# design.net
KiCad netlist of a schematic drawn in Altium Designer
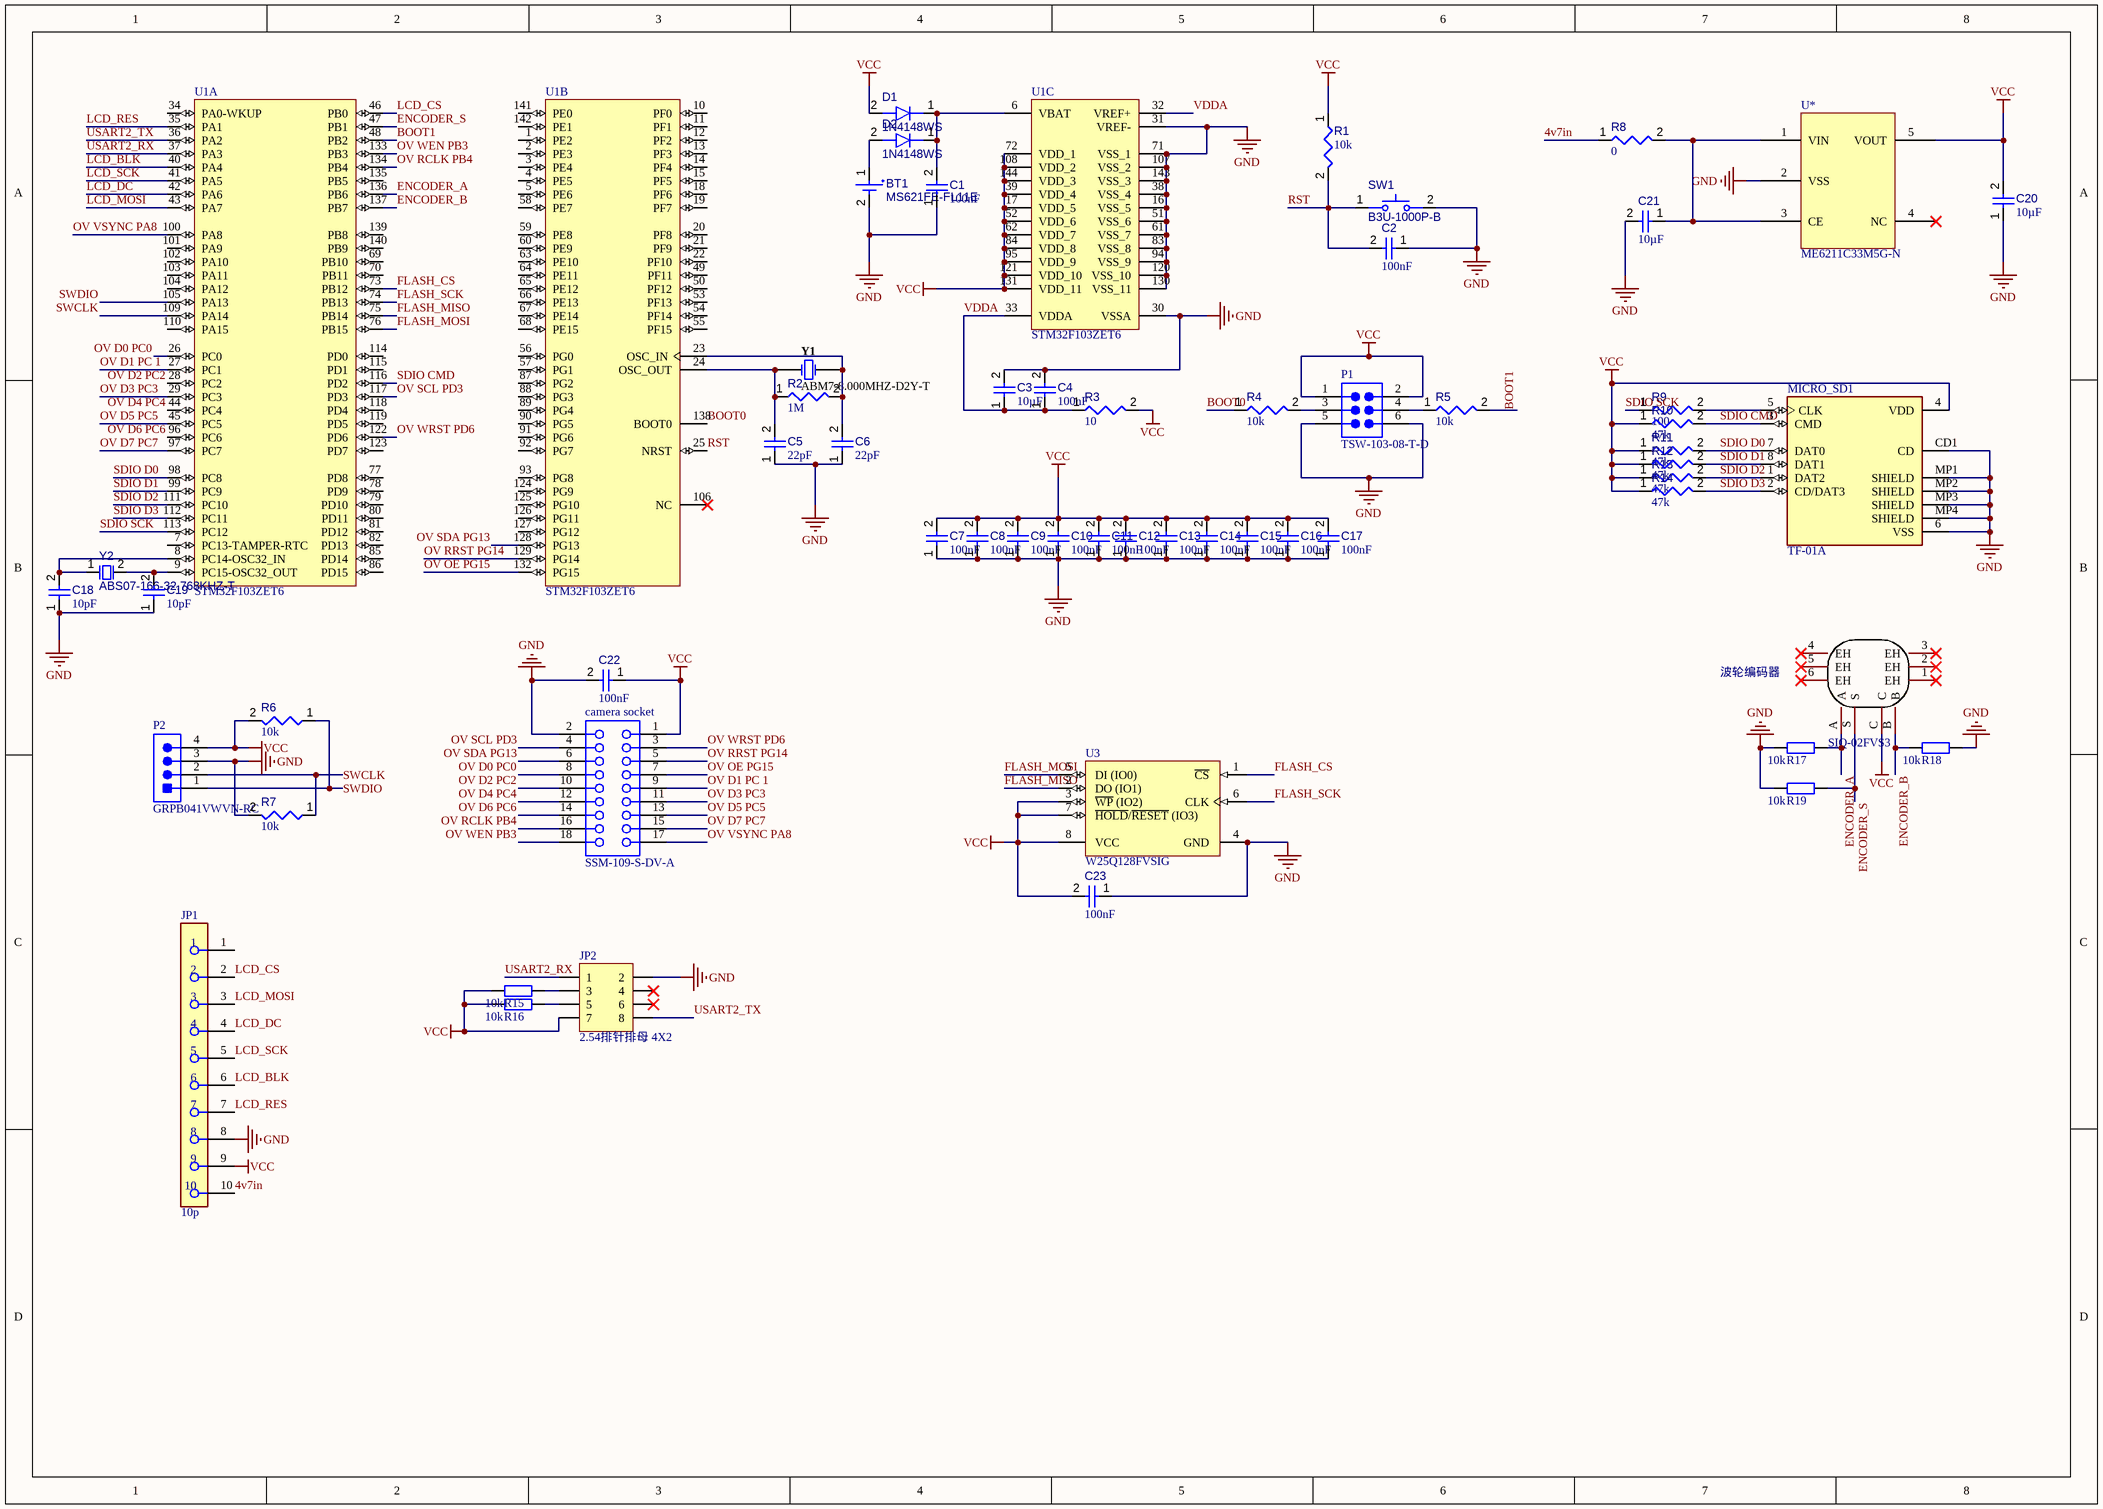
[diagram p0: 前板.SchDoc]

(export (version "E")
  (design (tool "Eeschema 10.0.6"))
  (components
    (comp (ref "BT1")
      (value "MS621FE-FL11E")
      (footprint "SEIK-MS621FE-FL11E-2_V")
      (description "MS Lihium Rechargeable Battery, 3 V, -20 to 60 degC, Tray")
      (libsource (lib "DigiPCBA Workspace") (part "CMP-00622-2"))
    )
    (comp (ref "C1")
      (value "100nF")
      (footprint "CAPC1608X90X40NL10T20")
      (description "Chip Capacitor, 100 nF, +/- 10%, 50 V, 0603 (1608 Metric)")
      (fields (field (name "TOLERANCE") "10%") (field (name "Comment") "Capacitor 100 nF +/-10% 50 V 0603"))
      (libsource (lib "DigiPCBA Workspace") (part "CAP-NP-2"))
    )
    (comp (ref "C2")
      (value "100nF")
      (footprint "CAPC1608X90X40NL10T20")
      (description "Chip Capacitor, 100 nF, +/- 10%, 50 V, 0603 (1608 Metric)")
      (fields (field (name "TOLERANCE") "10%") (field (name "Comment") "Capacitor 100 nF +/-10% 50 V 0603"))
      (libsource (lib "DigiPCBA Workspace") (part "CAP-NP-2"))
    )
    (comp (ref "C3")
      (value "10µF")
      (footprint "CAPC0603(1608)100_L")
      (description "Chip Capacitor, 10µF +/-20%, 10V, 0603, Thickness 1 mm")
      (fields (field (name "TOLERANCE") "10%") (field (name "Comment") "Capacitor 10µF +/-20% 10V 0603"))
      (libsource (lib "DigiPCBA Workspace") (part "CAP-NP-2"))
    )
    (comp (ref "C4")
      (value "100nF")
      (footprint "CAPC1608X90X40NL10T20")
      (description "Chip Capacitor, 100 nF, +/- 10%, 50 V, 0603 (1608 Metric)")
      (fields (field (name "TOLERANCE") "10%") (field (name "Comment") "Capacitor 100 nF +/-10% 50 V 0603"))
      (libsource (lib "DigiPCBA Workspace") (part "CAP-NP-2"))
    )
    (comp (ref "C5")
      (value "22pF")
      (footprint "CAPC1608X90X35ML10T15")
      (description "CAP CER 22PF 50V C0G/NP0 0603")
      (fields (field (name "TOLERANCE") "10%") (field (name "Comment") "GRM1885C1H220JA01D"))
      (libsource (lib "DigiPCBA Workspace") (part "CAP-NP-2"))
    )
    (comp (ref "C6")
      (value "22pF")
      (footprint "CAPC1608X90X35ML10T15")
      (description "CAP CER 22PF 50V C0G/NP0 0603")
      (fields (field (name "TOLERANCE") "10%") (field (name "Comment") "GRM1885C1H220JA01D"))
      (libsource (lib "DigiPCBA Workspace") (part "CAP-NP-2"))
    )
    (comp (ref "C7")
      (value "100nF")
      (footprint "CAPC1608X90X40NL10T20")
      (description "Chip Capacitor, 100 nF, +/- 10%, 50 V, 0603 (1608 Metric)")
      (fields (field (name "TOLERANCE") "10%") (field (name "Comment") "Capacitor 100 nF +/-10% 50 V 0603"))
      (libsource (lib "DigiPCBA Workspace") (part "CAP-NP-2"))
    )
    (comp (ref "C8")
      (value "100nF")
      (footprint "CAPC1608X90X40NL10T20")
      (description "Chip Capacitor, 100 nF, +/- 10%, 50 V, 0603 (1608 Metric)")
      (fields (field (name "TOLERANCE") "10%") (field (name "Comment") "Capacitor 100 nF +/-10% 50 V 0603"))
      (libsource (lib "DigiPCBA Workspace") (part "CAP-NP-2"))
    )
    (comp (ref "C9")
      (value "100nF")
      (footprint "CAPC1608X90X40NL10T20")
      (description "Chip Capacitor, 100 nF, +/- 10%, 50 V, 0603 (1608 Metric)")
      (fields (field (name "TOLERANCE") "10%") (field (name "Comment") "Capacitor 100 nF +/-10% 50 V 0603"))
      (libsource (lib "DigiPCBA Workspace") (part "CAP-NP-2"))
    )
    (comp (ref "C10")
      (value "100nF")
      (footprint "CAPC1608X90X40NL10T20")
      (description "Chip Capacitor, 100 nF, +/- 10%, 50 V, 0603 (1608 Metric)")
      (fields (field (name "TOLERANCE") "10%") (field (name "Comment") "Capacitor 100 nF +/-10% 50 V 0603"))
      (libsource (lib "DigiPCBA Workspace") (part "CAP-NP-2"))
    )
    (comp (ref "C11")
      (value "100nF")
      (footprint "CAPC1608X90X40NL10T20")
      (description "Chip Capacitor, 100 nF, +/- 10%, 50 V, 0603 (1608 Metric)")
      (fields (field (name "TOLERANCE") "10%") (field (name "Comment") "Capacitor 100 nF +/-10% 50 V 0603"))
      (libsource (lib "DigiPCBA Workspace") (part "CAP-NP-2"))
    )
    (comp (ref "C12")
      (value "100nF")
      (footprint "CAPC1608X90X40NL10T20")
      (description "Chip Capacitor, 100 nF, +/- 10%, 50 V, 0603 (1608 Metric)")
      (fields (field (name "TOLERANCE") "10%") (field (name "Comment") "Capacitor 100 nF +/-10% 50 V 0603"))
      (libsource (lib "DigiPCBA Workspace") (part "CAP-NP-2"))
    )
    (comp (ref "C13")
      (value "100nF")
      (footprint "CAPC1608X90X40NL10T20")
      (description "Chip Capacitor, 100 nF, +/- 10%, 50 V, 0603 (1608 Metric)")
      (fields (field (name "TOLERANCE") "10%") (field (name "Comment") "Capacitor 100 nF +/-10% 50 V 0603"))
      (libsource (lib "DigiPCBA Workspace") (part "CAP-NP-2"))
    )
    (comp (ref "C14")
      (value "100nF")
      (footprint "CAPC1608X90X40NL10T20")
      (description "Chip Capacitor, 100 nF, +/- 10%, 50 V, 0603 (1608 Metric)")
      (fields (field (name "TOLERANCE") "10%") (field (name "Comment") "Capacitor 100 nF +/-10% 50 V 0603"))
      (libsource (lib "DigiPCBA Workspace") (part "CAP-NP-2"))
    )
    (comp (ref "C15")
      (value "100nF")
      (footprint "CAPC1608X90X40NL10T20")
      (description "Chip Capacitor, 100 nF, +/- 10%, 50 V, 0603 (1608 Metric)")
      (fields (field (name "TOLERANCE") "10%") (field (name "Comment") "Capacitor 100 nF +/-10% 50 V 0603"))
      (libsource (lib "DigiPCBA Workspace") (part "CAP-NP-2"))
    )
    (comp (ref "C16")
      (value "100nF")
      (footprint "CAPC1608X90X40NL10T20")
      (description "Chip Capacitor, 100 nF, +/- 10%, 50 V, 0603 (1608 Metric)")
      (fields (field (name "TOLERANCE") "10%") (field (name "Comment") "Capacitor 100 nF +/-10% 50 V 0603"))
      (libsource (lib "DigiPCBA Workspace") (part "CAP-NP-2"))
    )
    (comp (ref "C17")
      (value "100nF")
      (footprint "CAPC1608X90X40NL10T20")
      (description "Chip Capacitor, 100 nF, +/- 10%, 50 V, 0603 (1608 Metric)")
      (fields (field (name "TOLERANCE") "10%") (field (name "Comment") "Capacitor 100 nF +/-10% 50 V 0603"))
      (libsource (lib "DigiPCBA Workspace") (part "CAP-NP-2"))
    )
    (comp (ref "C18")
      (value "10pF")
      (footprint "CAPC1005X55X25ML05T05")
      (description "Chip Capacitor, 10 pF, +/- 5%, 50 V, 0402 (1005 Metric)")
      (fields (field (name "TOLERANCE") "5%") (field (name "Comment") "Capacitor 10 pF +/- 5% 50 V 0402"))
      (libsource (lib "DigiPCBA Workspace") (part "CAP-NP-2"))
    )
    (comp (ref "C19")
      (value "10pF")
      (footprint "CAPC1005X55X25ML05T05")
      (description "Chip Capacitor, 10 pF, +/- 5%, 50 V, 0402 (1005 Metric)")
      (fields (field (name "TOLERANCE") "5%") (field (name "Comment") "Capacitor 10 pF +/- 5% 50 V 0402"))
      (libsource (lib "DigiPCBA Workspace") (part "CAP-NP-2"))
    )
    (comp (ref "C20")
      (value "10µF")
      (footprint "CAPC0603(1608)100_L")
      (description "Chip Capacitor, 10µF +/-20%, 10V, 0603, Thickness 1 mm")
      (fields (field (name "TOLERANCE") "10%") (field (name "Comment") "Capacitor 10µF +/-20% 10V 0603"))
      (libsource (lib "DigiPCBA Workspace") (part "CAP-NP-2"))
    )
    (comp (ref "C21")
      (value "10µF")
      (footprint "CAPC0603(1608)100_L")
      (description "Chip Capacitor, 10µF +/-20%, 10V, 0603, Thickness 1 mm")
      (fields (field (name "TOLERANCE") "10%") (field (name "Comment") "Capacitor 10µF +/-20% 10V 0603"))
      (libsource (lib "DigiPCBA Workspace") (part "CAP-NP-2"))
    )
    (comp (ref "C22")
      (value "100nF")
      (footprint "CAPC1608X90X40NL10T20")
      (description "Chip Capacitor, 100 nF, +/- 10%, 50 V, 0603 (1608 Metric)")
      (fields (field (name "TOLERANCE") "10%") (field (name "Comment") "Capacitor 100 nF +/-10% 50 V 0603"))
      (libsource (lib "DigiPCBA Workspace") (part "CAP-NP-2"))
    )
    (comp (ref "C23")
      (value "100nF")
      (footprint "CAPC1608X90X40NL10T20")
      (description "Chip Capacitor, 100 nF, +/- 10%, 50 V, 0603 (1608 Metric)")
      (fields (field (name "TOLERANCE") "10%") (field (name "Comment") "Capacitor 100 nF +/-10% 50 V 0603"))
      (libsource (lib "DigiPCBA Workspace") (part "CAP-NP-2"))
    )
    (comp (ref "camera socket")
      (value "SSM-109-S-DV-A")
      (footprint "SMTC-SSM-109-X-DV-A")
      (description "Headers & Wire Housings Surface Mount PCB Socket Strips, 0.100 pitch")
      (libsource (lib "DigiPCBA Workspace") (part "SMTC-SSM-109-X-DV-A"))
    )
    (comp (ref "D1")
      (value "1N4148WS")
      (footprint "FP-477AB-IPC_A")
      (description "Diode Ultra Fast Recovery Rectifier 75V 0.15A 2-Pin SOD-323F T/R")
      (libsource (lib "DigiPCBA Workspace") (part "DIODE-2"))
    )
    (comp (ref "D2")
      (value "1N4148WS")
      (footprint "FP-477AB-IPC_A")
      (description "Diode Ultra Fast Recovery Rectifier 75V 0.15A 2-Pin SOD-323F T/R")
      (libsource (lib "DigiPCBA Workspace") (part "DIODE-2"))
    )
    (comp (ref "JP1")
      (value "10p")
      (footprint "XH2.54-WI-10P")
      (fields (field (name "SOURCE") "线对板线对线连接器.SchLib"))
      (libsource (lib "DigiPCBA Workspace") (part "10p"))
    )
    (comp (ref "JP2")
      (value "2.54排针排母 4X2")
      (footprint "HDR2.54-LI-2x4P")
      (description "4*2P接插件")
      (libsource (lib "DigiPCBA Workspace") (part "Header 4X2"))
    )
    (comp (ref "MICRO_SD1")
      (value "TF-01A")
      (footprint "TF-01A")
      (description "Standard Card Edge Connectors")
      (fields (field (name "MF") "HRO Electronics Co., Ltd."))
      (libsource (lib "DigiPCBA Workspace") (part "TF-01A"))
    )
    (comp (ref "P1")
      (value "TSW-103-08-T-D")
      (footprint "SMTC-TSW-103-08-X-D")
      (description "Headers & Wire Housings Classic PCB Header Strips, 0.100 pitch")
      (libsource (lib "DigiPCBA Workspace") (part "SMTC-TSW-103-08-X-D"))
    )
    (comp (ref "P2")
      (value "GRPB041VWVN-RC")
      (footprint "SLIN-GRPB041VWVN-RC_V")
      (description "Male, 4 C, Straight, .050\" CC; 3.00mm Head/2.30mm Tail, No Mt; Nylon 9T, Brass, 105 C")
      (libsource (lib "DigiPCBA Workspace") (part "CN-1P-M-R4"))
    )
    (comp (ref "R1")
      (value "10k")
      (footprint "RESC1608X55X25ML10T15")
      (description "Chip Resistor, 10 KOhm, +/- 1%, 01 W, -55 to 155 degC, 0603 (1608 Metric)")
      (fields (field (name "POWER") "100mW") (field (name "TOLERANCE") "1%"))
      (libsource (lib "DigiPCBA Workspace") (part "RES-2"))
    )
    (comp (ref "R2")
      (value "1M")
      (footprint "FP-ERJ3EK-IPC_A")
      (description "Res Thick Film 0603 1M Ohm 1% 1/10W ±100ppm/°C Molded SMD Punched Carrier T/R")
      (fields (field (name "TOLERANCE") "1%") (field (name "Comment") "ERJ-3EKF1004V"))
      (libsource (lib "DigiPCBA Workspace") (part "RES-2"))
    )
    (comp (ref "R3")
      (value "10")
      (footprint "RESC0603(1608)_L")
      (description "Res Thick Film 0603 10 Ohm 1% 0.1W(1/10W) +/-100ppm/C Molded SMD Automotive Punched T/R")
      (fields (field (name "TOLERANCE") "1%") (field (name "Comment") "ERJ3EKF10R0V"))
      (libsource (lib "DigiPCBA Workspace") (part "RES-2"))
    )
    (comp (ref "R4")
      (value "10k")
      (footprint "RESC1608X55X25ML10T15")
      (description "Chip Resistor, 10 KOhm, +/- 1%, 01 W, -55 to 155 degC, 0603 (1608 Metric)")
      (fields (field (name "POWER") "100mW") (field (name "TOLERANCE") "1%"))
      (libsource (lib "DigiPCBA Workspace") (part "RES-2"))
    )
    (comp (ref "R5")
      (value "10k")
      (footprint "RESC1608X55X25ML10T15")
      (description "Chip Resistor, 10 KOhm, +/- 1%, 01 W, -55 to 155 degC, 0603 (1608 Metric)")
      (fields (field (name "POWER") "100mW") (field (name "TOLERANCE") "1%"))
      (libsource (lib "DigiPCBA Workspace") (part "RES-2"))
    )
    (comp (ref "R6")
      (value "10k")
      (footprint "RESC1608X55X25ML10T15")
      (description "Chip Resistor, 10 KOhm, +/- 1%, 01 W, -55 to 155 degC, 0603 (1608 Metric)")
      (fields (field (name "POWER") "100mW") (field (name "TOLERANCE") "1%"))
      (libsource (lib "DigiPCBA Workspace") (part "RES-2"))
    )
    (comp (ref "R7")
      (value "10k")
      (footprint "RESC1608X55X25ML10T15")
      (description "Chip Resistor, 10 KOhm, +/- 1%, 01 W, -55 to 155 degC, 0603 (1608 Metric)")
      (fields (field (name "POWER") "100mW") (field (name "TOLERANCE") "1%"))
      (libsource (lib "DigiPCBA Workspace") (part "RES-2"))
    )
    (comp (ref "R8")
      (value "0")
      (footprint "RESC0603(1608)_L")
      (description "Jumper 0603 (1608 Metric)")
      (fields (field (name "Comment") "0R3J"))
      (libsource (lib "DigiPCBA Workspace") (part "0R3J"))
    )
    (comp (ref "R9")
      (value "100")
      (footprint "FP-RC0603-0_55-MFG")
      (description "Res Thick Film 0603 100 Ohm 5% 1/10W ±100ppm/°C Molded SMD SMD Paper T/R")
      (fields (field (name "TOLERANCE") "5%") (field (name "Comment") "RC0603JR-07100RL"))
      (libsource (lib "DigiPCBA Workspace") (part "RES-2"))
    )
    (comp (ref "R10")
      (value "47k")
      (footprint "FP-CRCW0603-e3-IPC_C")
      (description "SMD Chip Resistor, 47 kOhm, ± 1%, 100 mW, 0603 [1608 Metric], Thick Film, General Purpose")
      (fields (field (name "TOLERANCE") "1%") (field (name "Comment") "CRCW060347K0FKEA"))
      (libsource (lib "DigiPCBA Workspace") (part "RES-2"))
    )
    (comp (ref "R11")
      (value "47k")
      (footprint "FP-CRCW0603-e3-IPC_C")
      (description "SMD Chip Resistor, 47 kOhm, ± 1%, 100 mW, 0603 [1608 Metric], Thick Film, General Purpose")
      (fields (field (name "TOLERANCE") "1%") (field (name "Comment") "CRCW060347K0FKEA"))
      (libsource (lib "DigiPCBA Workspace") (part "RES-2"))
    )
    (comp (ref "R12")
      (value "47k")
      (footprint "FP-CRCW0603-e3-IPC_C")
      (description "SMD Chip Resistor, 47 kOhm, ± 1%, 100 mW, 0603 [1608 Metric], Thick Film, General Purpose")
      (fields (field (name "TOLERANCE") "1%") (field (name "Comment") "CRCW060347K0FKEA"))
      (libsource (lib "DigiPCBA Workspace") (part "RES-2"))
    )
    (comp (ref "R13")
      (value "47k")
      (footprint "FP-CRCW0603-e3-IPC_C")
      (description "SMD Chip Resistor, 47 kOhm, ± 1%, 100 mW, 0603 [1608 Metric], Thick Film, General Purpose")
      (fields (field (name "TOLERANCE") "1%") (field (name "Comment") "CRCW060347K0FKEA"))
      (libsource (lib "DigiPCBA Workspace") (part "RES-2"))
    )
    (comp (ref "R14")
      (value "47k")
      (footprint "FP-CRCW0603-e3-IPC_C")
      (description "SMD Chip Resistor, 47 kOhm, ± 1%, 100 mW, 0603 [1608 Metric], Thick Film, General Purpose")
      (fields (field (name "TOLERANCE") "1%") (field (name "Comment") "CRCW060347K0FKEA"))
      (libsource (lib "DigiPCBA Workspace") (part "RES-2"))
    )
    (comp (ref "R15")
      (value "10k")
      (footprint "R 0603_L")
      (description "贴片电阻")
      (libsource (lib "DigiPCBA Workspace") (part "R-Precision"))
    )
    (comp (ref "R16")
      (value "10k")
      (footprint "R 0603_L")
      (description "贴片电阻")
      (libsource (lib "DigiPCBA Workspace") (part "R-Precision"))
    )
    (comp (ref "R17")
      (value "10k")
      (footprint "R 0603_L")
      (description "贴片电阻")
      (libsource (lib "DigiPCBA Workspace") (part "R-Precision"))
    )
    (comp (ref "R18")
      (value "10k")
      (footprint "R 0603_L")
      (description "贴片电阻")
      (libsource (lib "DigiPCBA Workspace") (part "R-Precision"))
    )
    (comp (ref "R19")
      (value "10k")
      (footprint "R 0603_L")
      (description "贴片电阻")
      (libsource (lib "DigiPCBA Workspace") (part "R-Precision"))
    )
    (comp (ref "SW1")
      (value "B3U-1000P-B")
      (footprint "OMRON-B3U-1000P-2-B_V")
      (libsource (lib "DigiPCBA Workspace") (part "CMP-00164-6"))
    )
    (comp (ref "U*")
      (value "ME6211C33M5G-N")
      (footprint "SOT23-5N")
      (description "VIN=6.5V Vo=3.3V Io=600mA")
      (libsource (lib "DigiPCBA Workspace") (part "ME6211C33M5G-N-Symbol-1"))
    )
    (comp (ref "U1")
      (value "STM32F103ZET6")
      (footprint "STM-LQFP144_N")
      (description "MCU 32-bit STM32F1 ARM Cortex M3 RISC 512KB Flash 2.5V/3.3V 144-Pin LQFP Tray")
      (libsource (lib "DigiPCBA Workspace") (part "MC-ARM-STM32F103XC_D_E-SQ144"))
    )
    (comp (ref "U2")
      (value "SIQ-02FVS3")
      (footprint "SW-SMD_SIQ-02FVS3_1")
      (fields (field (name "MANUFACTURER") "MITSUMI(美上美)"))
      (libsource (lib "DigiPCBA Workspace") (part "SIQ-02FVS3"))
    )
    (comp (ref "U3")
      (value "W25Q128FVSIG")
      (footprint "SOIC-8_208mil")
      (description "IC FLASH 128MBIT 104MHZ 8SOIC")
      (libsource (lib "DigiPCBA Workspace") (part "WINB-W25Q128FVSIG-SOIC-8"))
    )
    (comp (ref "Y1")
      (value "ABM7-8.000MHZ-D2Y-T")
      (footprint "FP-ABM7-MFG")
      (description "Crystal 8MHz ±20ppm (Tol) ±30ppm (Stability) 18pF FUND 100Ohm 2-Pin Mini-CSMD T/R")
      (libsource (lib "DigiPCBA Workspace") (part "XTAL-2"))
    )
    (comp (ref "Y2")
      (value "ABS07-166-32.768KHZ-T")
      (footprint "EPSON-FC-135_V")
      (description "Crystal 32.768kHz 10ppm 7pF -40C +85C")
      (libsource (lib "DigiPCBA Workspace") (part "CMP-001-0024-1"))
    )
  )
  (nets
    (net (code "1") (name "/4v7in") (class "Default")
      (node (ref "JP1") (pin "10") (pinfunction "10_10") (pintype "passive"))
      (node (ref "R8") (pin "1") (pinfunction "1_1") (pintype "passive"))
    )
    (net (code "2") (name "/BOOT0") (class "Default")
      (node (ref "R4") (pin "1") (pinfunction "1_1") (pintype "passive"))
      (node (ref "U1") (pin "138") (pinfunction "BOOT0_138") (pintype "input"))
    )
    (net (code "3") (name "/BOOT1") (class "Default")
      (node (ref "R5") (pin "2") (pinfunction "2_2") (pintype "passive"))
      (node (ref "U1") (pin "48") (pinfunction "PB2_48") (pintype "bidirectional"))
    )
    (net (code "4") (name "/ENCODER_A") (class "Default")
      (node (ref "R17") (pin "2") (pinfunction "2_2") (pintype "passive"))
      (node (ref "U1") (pin "136") (pinfunction "PB6_136") (pintype "bidirectional"))
      (node (ref "U2") (pin "A") (pinfunction "A_A") (pintype "passive"))
    )
    (net (code "5") (name "/ENCODER_B") (class "Default")
      (node (ref "R18") (pin "1") (pinfunction "1_1") (pintype "passive"))
      (node (ref "U1") (pin "137") (pinfunction "PB7_137") (pintype "bidirectional"))
      (node (ref "U2") (pin "B") (pinfunction "B_B") (pintype "passive"))
    )
    (net (code "6") (name "/ENCODER_S") (class "Default")
      (node (ref "R19") (pin "2") (pinfunction "2_2") (pintype "passive"))
      (node (ref "U1") (pin "47") (pinfunction "PB1_47") (pintype "bidirectional"))
      (node (ref "U2") (pin "S") (pinfunction "S_S") (pintype "passive"))
    )
    (net (code "7") (name "/FLASH_CS") (class "Default")
      (node (ref "U1") (pin "73") (pinfunction "PB12_73") (pintype "bidirectional"))
      (node (ref "U3") (pin "1") (pinfunction "~{CS}_1") (pintype "input"))
    )
    (net (code "8") (name "/FLASH_MISO") (class "Default")
      (node (ref "U1") (pin "75") (pinfunction "PB14_75") (pintype "bidirectional"))
      (node (ref "U3") (pin "2") (pinfunction "DO_(IO1)_2") (pintype "bidirectional"))
    )
    (net (code "9") (name "/FLASH_MOSI") (class "Default")
      (node (ref "U1") (pin "76") (pinfunction "PB15_76") (pintype "bidirectional"))
      (node (ref "U3") (pin "5") (pinfunction "DI_(IO0)_5") (pintype "bidirectional"))
    )
    (net (code "10") (name "/FLASH_SCK") (class "Default")
      (node (ref "U1") (pin "74") (pinfunction "PB13_74") (pintype "bidirectional"))
      (node (ref "U3") (pin "6") (pinfunction "CLK_6") (pintype "input"))
    )
    (net (code "11") (name "/LCD_BLK") (class "Default")
      (node (ref "JP1") (pin "6") (pinfunction "6_6") (pintype "passive"))
      (node (ref "U1") (pin "40") (pinfunction "PA4_40") (pintype "bidirectional"))
    )
    (net (code "12") (name "/LCD_CS") (class "Default")
      (node (ref "JP1") (pin "2") (pinfunction "2_2") (pintype "passive"))
      (node (ref "U1") (pin "46") (pinfunction "PB0_46") (pintype "bidirectional"))
    )
    (net (code "13") (name "/LCD_DC") (class "Default")
      (node (ref "JP1") (pin "4") (pinfunction "4_4") (pintype "passive"))
      (node (ref "U1") (pin "42") (pinfunction "PA6_42") (pintype "bidirectional"))
    )
    (net (code "14") (name "/LCD_MOSI") (class "Default")
      (node (ref "JP1") (pin "3") (pinfunction "3_3") (pintype "passive"))
      (node (ref "U1") (pin "43") (pinfunction "PA7_43") (pintype "bidirectional"))
    )
    (net (code "15") (name "/LCD_RES") (class "Default")
      (node (ref "JP1") (pin "7") (pinfunction "7_7") (pintype "passive"))
      (node (ref "U1") (pin "35") (pinfunction "PA1_35") (pintype "bidirectional"))
    )
    (net (code "16") (name "/LCD_SCK") (class "Default")
      (node (ref "JP1") (pin "5") (pinfunction "5_5") (pintype "passive"))
      (node (ref "U1") (pin "41") (pinfunction "PA5_41") (pintype "bidirectional"))
    )
    (net (code "17") (name "/OV D0 PC0") (class "Default")
      (node (ref "U1") (pin "26") (pinfunction "PC0_26") (pintype "bidirectional"))
      (node (ref "camera socket") (pin "8") (pinfunction "8_8") (pintype "passive"))
    )
    (net (code "18") (name "/OV D1 PC 1") (class "Default")
      (node (ref "U1") (pin "27") (pinfunction "PC1_27") (pintype "bidirectional"))
      (node (ref "camera socket") (pin "9") (pinfunction "9_9") (pintype "passive"))
    )
    (net (code "19") (name "/OV D2 PC2") (class "Default")
      (node (ref "U1") (pin "28") (pinfunction "PC2_28") (pintype "bidirectional"))
      (node (ref "camera socket") (pin "10") (pinfunction "10_10") (pintype "passive"))
    )
    (net (code "20") (name "/OV D3 PC3") (class "Default")
      (node (ref "U1") (pin "29") (pinfunction "PC3_29") (pintype "bidirectional"))
      (node (ref "camera socket") (pin "11") (pinfunction "11_11") (pintype "passive"))
    )
    (net (code "21") (name "/OV D4 PC4") (class "Default")
      (node (ref "U1") (pin "44") (pinfunction "PC4_44") (pintype "bidirectional"))
      (node (ref "camera socket") (pin "12") (pinfunction "12_12") (pintype "passive"))
    )
    (net (code "22") (name "/OV D5 PC5") (class "Default")
      (node (ref "U1") (pin "45") (pinfunction "PC5_45") (pintype "bidirectional"))
      (node (ref "camera socket") (pin "13") (pinfunction "13_13") (pintype "passive"))
    )
    (net (code "23") (name "/OV D6 PC6") (class "Default")
      (node (ref "U1") (pin "96") (pinfunction "PC6_96") (pintype "bidirectional"))
      (node (ref "camera socket") (pin "14") (pinfunction "14_14") (pintype "passive"))
    )
    (net (code "24") (name "/OV D7 PC7") (class "Default")
      (node (ref "U1") (pin "97") (pinfunction "PC7_97") (pintype "bidirectional"))
      (node (ref "camera socket") (pin "15") (pinfunction "15_15") (pintype "passive"))
    )
    (net (code "25") (name "/OV OE PG15") (class "Default")
      (node (ref "U1") (pin "132") (pinfunction "PG15_132") (pintype "bidirectional"))
      (node (ref "camera socket") (pin "7") (pinfunction "7_7") (pintype "passive"))
    )
    (net (code "26") (name "/OV RCLK PB4") (class "Default")
      (node (ref "U1") (pin "134") (pinfunction "PB4_134") (pintype "bidirectional"))
      (node (ref "camera socket") (pin "16") (pinfunction "16_16") (pintype "passive"))
    )
    (net (code "27") (name "/OV RRST PG14") (class "Default")
      (node (ref "U1") (pin "129") (pinfunction "PG14_129") (pintype "bidirectional"))
      (node (ref "camera socket") (pin "5") (pinfunction "5_5") (pintype "passive"))
    )
    (net (code "28") (name "/OV SCL PD3") (class "Default")
      (node (ref "U1") (pin "117") (pinfunction "PD3_117") (pintype "bidirectional"))
      (node (ref "camera socket") (pin "4") (pinfunction "4_4") (pintype "passive"))
    )
    (net (code "29") (name "/OV SDA PG13") (class "Default")
      (node (ref "U1") (pin "128") (pinfunction "PG13_128") (pintype "bidirectional"))
      (node (ref "camera socket") (pin "6") (pinfunction "6_6") (pintype "passive"))
    )
    (net (code "30") (name "/OV VSYNC PA8") (class "Default")
      (node (ref "U1") (pin "100") (pinfunction "PA8_100") (pintype "bidirectional"))
      (node (ref "camera socket") (pin "17") (pinfunction "17_17") (pintype "passive"))
    )
    (net (code "31") (name "/OV WEN PB3") (class "Default")
      (node (ref "U1") (pin "133") (pinfunction "PB3_133") (pintype "bidirectional"))
      (node (ref "camera socket") (pin "18") (pinfunction "18_18") (pintype "passive"))
    )
    (net (code "32") (name "/OV WRST PD6") (class "Default")
      (node (ref "U1") (pin "122") (pinfunction "PD6_122") (pintype "bidirectional"))
      (node (ref "camera socket") (pin "3") (pinfunction "3_3") (pintype "passive"))
    )
    (net (code "33") (name "/RST") (class "Default")
      (node (ref "C2") (pin "2") (pinfunction "2_2") (pintype "passive"))
      (node (ref "R1") (pin "2") (pinfunction "2_2") (pintype "passive"))
      (node (ref "SW1") (pin "1") (pinfunction "1_1") (pintype "passive"))
      (node (ref "U1") (pin "25") (pinfunction "NRST_25") (pintype "bidirectional"))
    )
    (net (code "34") (name "/SDIO CMD") (class "Default")
      (node (ref "MICRO_SD1") (pin "3") (pinfunction "CMD_3") (pintype "bidirectional"))
      (node (ref "R10") (pin "2") (pinfunction "2_2") (pintype "passive"))
      (node (ref "U1") (pin "116") (pinfunction "PD2_116") (pintype "bidirectional"))
    )
    (net (code "35") (name "/SDIO D0") (class "Default")
      (node (ref "MICRO_SD1") (pin "7") (pinfunction "DAT0_7") (pintype "bidirectional"))
      (node (ref "R11") (pin "2") (pinfunction "2_2") (pintype "passive"))
      (node (ref "U1") (pin "98") (pinfunction "PC8_98") (pintype "bidirectional"))
    )
    (net (code "36") (name "/SDIO D1") (class "Default")
      (node (ref "MICRO_SD1") (pin "8") (pinfunction "DAT1_8") (pintype "bidirectional"))
      (node (ref "R12") (pin "2") (pinfunction "2_2") (pintype "passive"))
      (node (ref "U1") (pin "99") (pinfunction "PC9_99") (pintype "bidirectional"))
    )
    (net (code "37") (name "/SDIO D2") (class "Default")
      (node (ref "MICRO_SD1") (pin "1") (pinfunction "DAT2_1") (pintype "bidirectional"))
      (node (ref "R13") (pin "2") (pinfunction "2_2") (pintype "passive"))
      (node (ref "U1") (pin "111") (pinfunction "PC10_111") (pintype "bidirectional"))
    )
    (net (code "38") (name "/SDIO D3") (class "Default")
      (node (ref "MICRO_SD1") (pin "2") (pinfunction "CD/DAT3_2") (pintype "bidirectional"))
      (node (ref "R14") (pin "2") (pinfunction "2_2") (pintype "passive"))
      (node (ref "U1") (pin "112") (pinfunction "PC11_112") (pintype "bidirectional"))
    )
    (net (code "39") (name "/SDIO SCK") (class "Default")
      (node (ref "R9") (pin "1") (pinfunction "1_1") (pintype "passive"))
      (node (ref "U1") (pin "113") (pinfunction "PC12_113") (pintype "bidirectional"))
    )
    (net (code "40") (name "/SWCLK") (class "Default")
      (node (ref "P2") (pin "2") (pinfunction "2_2") (pintype "passive"))
      (node (ref "R7") (pin "1") (pinfunction "1_1") (pintype "passive"))
      (node (ref "U1") (pin "109") (pinfunction "PA14_109") (pintype "bidirectional"))
    )
    (net (code "41") (name "/SWDIO") (class "Default")
      (node (ref "P2") (pin "1") (pinfunction "1_1") (pintype "passive"))
      (node (ref "R6") (pin "1") (pinfunction "1_1") (pintype "passive"))
      (node (ref "U1") (pin "105") (pinfunction "PA13_105") (pintype "bidirectional"))
    )
    (net (code "42") (name "/USART2_RX") (class "Default")
      (node (ref "JP2") (pin "1") (pinfunction "1_1") (pintype "passive"))
      (node (ref "U1") (pin "37") (pinfunction "PA3_37") (pintype "bidirectional"))
    )
    (net (code "43") (name "/USART2_TX") (class "Default")
      (node (ref "JP2") (pin "8") (pinfunction "8_8") (pintype "passive"))
      (node (ref "U1") (pin "36") (pinfunction "PA2_36") (pintype "bidirectional"))
    )
    (net (code "44") (name "/VDDA") (class "Default")
      (node (ref "C3") (pin "1") (pinfunction "1_1") (pintype "passive"))
      (node (ref "C4") (pin "1") (pinfunction "1_1") (pintype "passive"))
      (node (ref "R3") (pin "1") (pinfunction "1_1") (pintype "passive"))
      (node (ref "U1") (pin "32") (pinfunction "VREF+_32") (pintype "power_in"))
      (node (ref "U1") (pin "33") (pinfunction "VDDA_33") (pintype "power_in"))
    )
    (net (code "45") (name "GND") (class "Default")
      (node (ref "BT1") (pin "2") (pinfunction "-_2") (pintype "passive"))
      (node (ref "C1") (pin "1") (pinfunction "1_1") (pintype "passive"))
      (node (ref "C10") (pin "1") (pinfunction "1_1") (pintype "passive"))
      (node (ref "C11") (pin "1") (pinfunction "1_1") (pintype "passive"))
      (node (ref "C12") (pin "1") (pinfunction "1_1") (pintype "passive"))
      (node (ref "C13") (pin "1") (pinfunction "1_1") (pintype "passive"))
      (node (ref "C14") (pin "1") (pinfunction "1_1") (pintype "passive"))
      (node (ref "C15") (pin "1") (pinfunction "1_1") (pintype "passive"))
      (node (ref "C16") (pin "1") (pinfunction "1_1") (pintype "passive"))
      (node (ref "C17") (pin "1") (pinfunction "1_1") (pintype "passive"))
      (node (ref "C18") (pin "1") (pinfunction "1_1") (pintype "passive"))
      (node (ref "C19") (pin "1") (pinfunction "1_1") (pintype "passive"))
      (node (ref "C2") (pin "1") (pinfunction "1_1") (pintype "passive"))
      (node (ref "C20") (pin "1") (pinfunction "1_1") (pintype "passive"))
      (node (ref "C21") (pin "2") (pinfunction "2_2") (pintype "passive"))
      (node (ref "C22") (pin "2") (pinfunction "2_2") (pintype "passive"))
      (node (ref "C23") (pin "1") (pinfunction "1_1") (pintype "passive"))
      (node (ref "C3") (pin "2") (pinfunction "2_2") (pintype "passive"))
      (node (ref "C4") (pin "2") (pinfunction "2_2") (pintype "passive"))
      (node (ref "C5") (pin "1") (pinfunction "1_1") (pintype "passive"))
      (node (ref "C6") (pin "1") (pinfunction "1_1") (pintype "passive"))
      (node (ref "C7") (pin "1") (pinfunction "1_1") (pintype "passive"))
      (node (ref "C8") (pin "1") (pinfunction "1_1") (pintype "passive"))
      (node (ref "C9") (pin "1") (pinfunction "1_1") (pintype "passive"))
      (node (ref "JP1") (pin "8") (pinfunction "8_8") (pintype "passive"))
      (node (ref "JP2") (pin "2") (pinfunction "2_2") (pintype "passive"))
      (node (ref "MICRO_SD1") (pin "6") (pinfunction "VSS_6") (pintype "power_in"))
      (node (ref "MICRO_SD1") (pin "CD1") (pinfunction "CD_CD1") (pintype "passive"))
      (node (ref "MICRO_SD1") (pin "MP1") (pinfunction "SHIELD_MP1") (pintype "power_in"))
      (node (ref "MICRO_SD1") (pin "MP2") (pinfunction "SHIELD_MP2") (pintype "power_in"))
      (node (ref "MICRO_SD1") (pin "MP3") (pinfunction "SHIELD_MP3") (pintype "power_in"))
      (node (ref "MICRO_SD1") (pin "MP4") (pinfunction "SHIELD_MP4") (pintype "power_in"))
      (node (ref "P1") (pin "5") (pinfunction "5_5") (pintype "passive"))
      (node (ref "P1") (pin "6") (pinfunction "6_6") (pintype "passive"))
      (node (ref "P2") (pin "3") (pinfunction "3_3") (pintype "passive"))
      (node (ref "R17") (pin "1") (pinfunction "1_1") (pintype "passive"))
      (node (ref "R18") (pin "2") (pinfunction "2_2") (pintype "passive"))
      (node (ref "R19") (pin "1") (pinfunction "1_1") (pintype "passive"))
      (node (ref "R7") (pin "2") (pinfunction "2_2") (pintype "passive"))
      (node (ref "SW1") (pin "2") (pinfunction "2_2") (pintype "passive"))
      (node (ref "U*") (pin "2") (pinfunction "VSS_2") (pintype "passive"))
      (node (ref "U1") (pin "107") (pinfunction "VSS_2_107") (pintype "power_in"))
      (node (ref "U1") (pin "120") (pinfunction "VSS_10_120") (pintype "power_in"))
      (node (ref "U1") (pin "130") (pinfunction "VSS_11_130") (pintype "power_in"))
      (node (ref "U1") (pin "143") (pinfunction "VSS_3_143") (pintype "power_in"))
      (node (ref "U1") (pin "16") (pinfunction "VSS_5_16") (pintype "power_in"))
      (node (ref "U1") (pin "30") (pinfunction "VSSA_30") (pintype "power_in"))
      (node (ref "U1") (pin "31") (pinfunction "VREF-_31") (pintype "power_in"))
      (node (ref "U1") (pin "38") (pinfunction "VSS_4_38") (pintype "power_in"))
      (node (ref "U1") (pin "51") (pinfunction "VSS_6_51") (pintype "power_in"))
      (node (ref "U1") (pin "61") (pinfunction "VSS_7_61") (pintype "power_in"))
      (node (ref "U1") (pin "71") (pinfunction "VSS_1_71") (pintype "power_in"))
      (node (ref "U1") (pin "83") (pinfunction "VSS_8_83") (pintype "power_in"))
      (node (ref "U1") (pin "94") (pinfunction "VSS_9_94") (pintype "power_in"))
      (node (ref "U3") (pin "4") (pinfunction "GND_4") (pintype "power_in"))
      (node (ref "camera socket") (pin "2") (pinfunction "2_2") (pintype "passive"))
    )
    (net (code "46") (name "Net-(BT1-+)") (class "Default")
      (node (ref "BT1") (pin "1") (pinfunction "+_1") (pintype "passive"))
      (node (ref "D2") (pin "2") (pinfunction "A_2") (pintype "passive"))
    )
    (net (code "47") (name "Net-(D1-K)") (class "Default")
      (node (ref "C1") (pin "2") (pinfunction "2_2") (pintype "passive"))
      (node (ref "D1") (pin "1") (pinfunction "K_1") (pintype "passive"))
      (node (ref "D2") (pin "1") (pinfunction "K_1") (pintype "passive"))
      (node (ref "U1") (pin "6") (pinfunction "VBAT_6") (pintype "power_in"))
    )
    (net (code "48") (name "Net-(JP2-Pad3)") (class "Default")
      (node (ref "JP2") (pin "3") (pinfunction "3_3") (pintype "passive"))
      (node (ref "R15") (pin "2") (pinfunction "2_2") (pintype "passive"))
    )
    (net (code "49") (name "Net-(JP2-Pad5)") (class "Default")
      (node (ref "JP2") (pin "5") (pinfunction "5_5") (pintype "passive"))
      (node (ref "R16") (pin "2") (pinfunction "2_2") (pintype "passive"))
    )
    (net (code "50") (name "Net-(MICRO_SD1-CLK)") (class "Default")
      (node (ref "MICRO_SD1") (pin "5") (pinfunction "CLK_5") (pintype "bidirectional"))
      (node (ref "R9") (pin "2") (pinfunction "2_2") (pintype "passive"))
    )
    (net (code "51") (name "Net-(P1-Pad3)") (class "Default")
      (node (ref "P1") (pin "3") (pinfunction "3_3") (pintype "passive"))
      (node (ref "R4") (pin "2") (pinfunction "2_2") (pintype "passive"))
    )
    (net (code "52") (name "Net-(P1-Pad4)") (class "Default")
      (node (ref "P1") (pin "4") (pinfunction "4_4") (pintype "passive"))
      (node (ref "R5") (pin "1") (pinfunction "1_1") (pintype "passive"))
    )
    (net (code "53") (name "Net-(U*-CE)") (class "Default")
      (node (ref "C21") (pin "1") (pinfunction "1_1") (pintype "passive"))
      (node (ref "R8") (pin "2") (pinfunction "2_2") (pintype "passive"))
      (node (ref "U*") (pin "1") (pinfunction "VIN_1") (pintype "passive"))
      (node (ref "U*") (pin "3") (pinfunction "CE_3") (pintype "passive"))
    )
    (net (code "54") (name "Net-(U1A-PC14-OSC32_IN)") (class "Default")
      (node (ref "C18") (pin "2") (pinfunction "2_2") (pintype "passive"))
      (node (ref "U1") (pin "8") (pinfunction "PC14-OSC32_IN_8") (pintype "bidirectional"))
      (node (ref "Y2") (pin "1") (pinfunction "1_1") (pintype "passive"))
    )
    (net (code "55") (name "Net-(U1A-PC15-OSC32_OUT)") (class "Default")
      (node (ref "C19") (pin "2") (pinfunction "2_2") (pintype "passive"))
      (node (ref "U1") (pin "9") (pinfunction "PC15-OSC32_OUT_9") (pintype "bidirectional"))
      (node (ref "Y2") (pin "2") (pinfunction "2_2") (pintype "passive"))
    )
    (net (code "56") (name "Net-(U1B-OSC_IN)") (class "Default")
      (node (ref "C6") (pin "2") (pinfunction "2_2") (pintype "passive"))
      (node (ref "R2") (pin "2") (pinfunction "2_2") (pintype "passive"))
      (node (ref "U1") (pin "23") (pinfunction "OSC_IN_23") (pintype "input"))
      (node (ref "Y1") (pin "2") (pinfunction "2_2") (pintype "passive"))
    )
    (net (code "57") (name "Net-(U1B-OSC_OUT)") (class "Default")
      (node (ref "C5") (pin "2") (pinfunction "2_2") (pintype "passive"))
      (node (ref "R2") (pin "1") (pinfunction "1_1") (pintype "passive"))
      (node (ref "U1") (pin "24") (pinfunction "OSC_OUT_24") (pintype "passive"))
      (node (ref "Y1") (pin "1") (pinfunction "1_1") (pintype "passive"))
    )
    (net (code "58") (name "VCC") (class "Default")
      (node (ref "C10") (pin "2") (pinfunction "2_2") (pintype "passive"))
      (node (ref "C11") (pin "2") (pinfunction "2_2") (pintype "passive"))
      (node (ref "C12") (pin "2") (pinfunction "2_2") (pintype "passive"))
      (node (ref "C13") (pin "2") (pinfunction "2_2") (pintype "passive"))
      (node (ref "C14") (pin "2") (pinfunction "2_2") (pintype "passive"))
      (node (ref "C15") (pin "2") (pinfunction "2_2") (pintype "passive"))
      (node (ref "C16") (pin "2") (pinfunction "2_2") (pintype "passive"))
      (node (ref "C17") (pin "2") (pinfunction "2_2") (pintype "passive"))
      (node (ref "C20") (pin "2") (pinfunction "2_2") (pintype "passive"))
      (node (ref "C22") (pin "1") (pinfunction "1_1") (pintype "passive"))
      (node (ref "C23") (pin "2") (pinfunction "2_2") (pintype "passive"))
      (node (ref "C7") (pin "2") (pinfunction "2_2") (pintype "passive"))
      (node (ref "C8") (pin "2") (pinfunction "2_2") (pintype "passive"))
      (node (ref "C9") (pin "2") (pinfunction "2_2") (pintype "passive"))
      (node (ref "D1") (pin "2") (pinfunction "A_2") (pintype "passive"))
      (node (ref "JP1") (pin "9") (pinfunction "9_9") (pintype "passive"))
      (node (ref "JP2") (pin "7") (pinfunction "7_7") (pintype "passive"))
      (node (ref "MICRO_SD1") (pin "4") (pinfunction "VDD_4") (pintype "power_in"))
      (node (ref "P1") (pin "1") (pinfunction "1_1") (pintype "passive"))
      (node (ref "P1") (pin "2") (pinfunction "2_2") (pintype "passive"))
      (node (ref "P2") (pin "4") (pinfunction "4_4") (pintype "passive"))
      (node (ref "R1") (pin "1") (pinfunction "1_1") (pintype "passive"))
      (node (ref "R10") (pin "1") (pinfunction "1_1") (pintype "passive"))
      (node (ref "R11") (pin "1") (pinfunction "1_1") (pintype "passive"))
      (node (ref "R12") (pin "1") (pinfunction "1_1") (pintype "passive"))
      (node (ref "R13") (pin "1") (pinfunction "1_1") (pintype "passive"))
      (node (ref "R14") (pin "1") (pinfunction "1_1") (pintype "passive"))
      (node (ref "R15") (pin "1") (pinfunction "1_1") (pintype "passive"))
      (node (ref "R16") (pin "1") (pinfunction "1_1") (pintype "passive"))
      (node (ref "R3") (pin "2") (pinfunction "2_2") (pintype "passive"))
      (node (ref "R6") (pin "2") (pinfunction "2_2") (pintype "passive"))
      (node (ref "U*") (pin "5") (pinfunction "VOUT_5") (pintype "passive"))
      (node (ref "U1") (pin "108") (pinfunction "VDD_2_108") (pintype "power_in"))
      (node (ref "U1") (pin "121") (pinfunction "VDD_10_121") (pintype "power_in"))
      (node (ref "U1") (pin "131") (pinfunction "VDD_11_131") (pintype "power_in"))
      (node (ref "U1") (pin "144") (pinfunction "VDD_3_144") (pintype "power_in"))
      (node (ref "U1") (pin "17") (pinfunction "VDD_5_17") (pintype "power_in"))
      (node (ref "U1") (pin "39") (pinfunction "VDD_4_39") (pintype "power_in"))
      (node (ref "U1") (pin "52") (pinfunction "VDD_6_52") (pintype "power_in"))
      (node (ref "U1") (pin "62") (pinfunction "VDD_7_62") (pintype "power_in"))
      (node (ref "U1") (pin "72") (pinfunction "VDD_1_72") (pintype "power_in"))
      (node (ref "U1") (pin "84") (pinfunction "VDD_8_84") (pintype "power_in"))
      (node (ref "U1") (pin "95") (pinfunction "VDD_9_95") (pintype "power_in"))
      (node (ref "U2") (pin "C") (pinfunction "C_C") (pintype "passive"))
      (node (ref "U3") (pin "3") (pinfunction "~{WP}_(IO2)_3") (pintype "bidirectional"))
      (node (ref "U3") (pin "7") (pinfunction "~{HOLD}/~{RESET}_(IO3)_7") (pintype "bidirectional"))
      (node (ref "U3") (pin "8") (pinfunction "VCC_8") (pintype "power_in"))
      (node (ref "camera socket") (pin "1") (pinfunction "1_1") (pintype "passive"))
    )
    (net (code "59") (name "unconnected-(JP1-Pad1)") (class "Default")
      (node (ref "JP1") (pin "1") (pinfunction "1_1") (pintype "passive"))
    )
    (net (code "60") (name "unconnected-(JP2-Pad4)") (class "Default")
      (node (ref "JP2") (pin "4") (pinfunction "4_4") (pintype "passive+no_connect"))
    )
    (net (code "61") (name "unconnected-(JP2-Pad6)") (class "Default")
      (node (ref "JP2") (pin "6") (pinfunction "6_6") (pintype "passive+no_connect"))
    )
    (net (code "62") (name "unconnected-(U*-NC-Pad4)") (class "Default")
      (node (ref "U*") (pin "4") (pinfunction "NC_4") (pintype "passive+no_connect"))
    )
    (net (code "63") (name "unconnected-(U1A-PA0-WKUP-Pad34)") (class "Default")
      (node (ref "U1") (pin "34") (pinfunction "PA0-WKUP_34") (pintype "bidirectional"))
    )
    (net (code "64") (name "unconnected-(U1A-PA9-Pad101)") (class "Default")
      (node (ref "U1") (pin "101") (pinfunction "PA9_101") (pintype "bidirectional"))
    )
    (net (code "65") (name "unconnected-(U1A-PA10-Pad102)") (class "Default")
      (node (ref "U1") (pin "102") (pinfunction "PA10_102") (pintype "bidirectional"))
    )
    (net (code "66") (name "unconnected-(U1A-PA11-Pad103)") (class "Default")
      (node (ref "U1") (pin "103") (pinfunction "PA11_103") (pintype "bidirectional"))
    )
    (net (code "67") (name "unconnected-(U1A-PA12-Pad104)") (class "Default")
      (node (ref "U1") (pin "104") (pinfunction "PA12_104") (pintype "bidirectional"))
    )
    (net (code "68") (name "unconnected-(U1A-PA15-Pad110)") (class "Default")
      (node (ref "U1") (pin "110") (pinfunction "PA15_110") (pintype "bidirectional"))
    )
    (net (code "69") (name "unconnected-(U1A-PB5-Pad135)") (class "Default")
      (node (ref "U1") (pin "135") (pinfunction "PB5_135") (pintype "bidirectional"))
    )
    (net (code "70") (name "unconnected-(U1A-PB8-Pad139)") (class "Default")
      (node (ref "U1") (pin "139") (pinfunction "PB8_139") (pintype "bidirectional"))
    )
    (net (code "71") (name "unconnected-(U1A-PB9-Pad140)") (class "Default")
      (node (ref "U1") (pin "140") (pinfunction "PB9_140") (pintype "bidirectional"))
    )
    (net (code "72") (name "unconnected-(U1A-PB10-Pad69)") (class "Default")
      (node (ref "U1") (pin "69") (pinfunction "PB10_69") (pintype "bidirectional"))
    )
    (net (code "73") (name "unconnected-(U1A-PB11-Pad70)") (class "Default")
      (node (ref "U1") (pin "70") (pinfunction "PB11_70") (pintype "bidirectional"))
    )
    (net (code "74") (name "unconnected-(U1A-PC13-TAMPER-RTC-Pad7)") (class "Default")
      (node (ref "U1") (pin "7") (pinfunction "PC13-TAMPER-RTC_7") (pintype "bidirectional"))
    )
    (net (code "75") (name "unconnected-(U1A-PD0-Pad114)") (class "Default")
      (node (ref "U1") (pin "114") (pinfunction "PD0_114") (pintype "bidirectional"))
    )
    (net (code "76") (name "unconnected-(U1A-PD1-Pad115)") (class "Default")
      (node (ref "U1") (pin "115") (pinfunction "PD1_115") (pintype "bidirectional"))
    )
    (net (code "77") (name "unconnected-(U1A-PD4-Pad118)") (class "Default")
      (node (ref "U1") (pin "118") (pinfunction "PD4_118") (pintype "bidirectional"))
    )
    (net (code "78") (name "unconnected-(U1A-PD5-Pad119)") (class "Default")
      (node (ref "U1") (pin "119") (pinfunction "PD5_119") (pintype "bidirectional"))
    )
    (net (code "79") (name "unconnected-(U1A-PD7-Pad123)") (class "Default")
      (node (ref "U1") (pin "123") (pinfunction "PD7_123") (pintype "bidirectional"))
    )
    (net (code "80") (name "unconnected-(U1A-PD8-Pad77)") (class "Default")
      (node (ref "U1") (pin "77") (pinfunction "PD8_77") (pintype "bidirectional"))
    )
    (net (code "81") (name "unconnected-(U1A-PD9-Pad78)") (class "Default")
      (node (ref "U1") (pin "78") (pinfunction "PD9_78") (pintype "bidirectional"))
    )
    (net (code "82") (name "unconnected-(U1A-PD10-Pad79)") (class "Default")
      (node (ref "U1") (pin "79") (pinfunction "PD10_79") (pintype "bidirectional"))
    )
    (net (code "83") (name "unconnected-(U1A-PD11-Pad80)") (class "Default")
      (node (ref "U1") (pin "80") (pinfunction "PD11_80") (pintype "bidirectional"))
    )
    (net (code "84") (name "unconnected-(U1A-PD12-Pad81)") (class "Default")
      (node (ref "U1") (pin "81") (pinfunction "PD12_81") (pintype "bidirectional"))
    )
    (net (code "85") (name "unconnected-(U1A-PD13-Pad82)") (class "Default")
      (node (ref "U1") (pin "82") (pinfunction "PD13_82") (pintype "bidirectional"))
    )
    (net (code "86") (name "unconnected-(U1A-PD14-Pad85)") (class "Default")
      (node (ref "U1") (pin "85") (pinfunction "PD14_85") (pintype "bidirectional"))
    )
    (net (code "87") (name "unconnected-(U1A-PD15-Pad86)") (class "Default")
      (node (ref "U1") (pin "86") (pinfunction "PD15_86") (pintype "bidirectional"))
    )
    (net (code "88") (name "unconnected-(U1B-NC-Pad106)") (class "Default")
      (node (ref "U1") (pin "106") (pinfunction "NC_106") (pintype "passive+no_connect"))
    )
    (net (code "89") (name "unconnected-(U1B-PE0-Pad141)") (class "Default")
      (node (ref "U1") (pin "141") (pinfunction "PE0_141") (pintype "bidirectional"))
    )
    (net (code "90") (name "unconnected-(U1B-PE1-Pad142)") (class "Default")
      (node (ref "U1") (pin "142") (pinfunction "PE1_142") (pintype "bidirectional"))
    )
    (net (code "91") (name "unconnected-(U1B-PE2-Pad1)") (class "Default")
      (node (ref "U1") (pin "1") (pinfunction "PE2_1") (pintype "bidirectional"))
    )
    (net (code "92") (name "unconnected-(U1B-PE3-Pad2)") (class "Default")
      (node (ref "U1") (pin "2") (pinfunction "PE3_2") (pintype "bidirectional"))
    )
    (net (code "93") (name "unconnected-(U1B-PE4-Pad3)") (class "Default")
      (node (ref "U1") (pin "3") (pinfunction "PE4_3") (pintype "bidirectional"))
    )
    (net (code "94") (name "unconnected-(U1B-PE5-Pad4)") (class "Default")
      (node (ref "U1") (pin "4") (pinfunction "PE5_4") (pintype "bidirectional"))
    )
    (net (code "95") (name "unconnected-(U1B-PE6-Pad5)") (class "Default")
      (node (ref "U1") (pin "5") (pinfunction "PE6_5") (pintype "bidirectional"))
    )
    (net (code "96") (name "unconnected-(U1B-PE7-Pad58)") (class "Default")
      (node (ref "U1") (pin "58") (pinfunction "PE7_58") (pintype "bidirectional"))
    )
    (net (code "97") (name "unconnected-(U1B-PE8-Pad59)") (class "Default")
      (node (ref "U1") (pin "59") (pinfunction "PE8_59") (pintype "bidirectional"))
    )
    (net (code "98") (name "unconnected-(U1B-PE9-Pad60)") (class "Default")
      (node (ref "U1") (pin "60") (pinfunction "PE9_60") (pintype "bidirectional"))
    )
    (net (code "99") (name "unconnected-(U1B-PE10-Pad63)") (class "Default")
      (node (ref "U1") (pin "63") (pinfunction "PE10_63") (pintype "bidirectional"))
    )
    (net (code "100") (name "unconnected-(U1B-PE11-Pad64)") (class "Default")
      (node (ref "U1") (pin "64") (pinfunction "PE11_64") (pintype "bidirectional"))
    )
    (net (code "101") (name "unconnected-(U1B-PE12-Pad65)") (class "Default")
      (node (ref "U1") (pin "65") (pinfunction "PE12_65") (pintype "bidirectional"))
    )
    (net (code "102") (name "unconnected-(U1B-PE13-Pad66)") (class "Default")
      (node (ref "U1") (pin "66") (pinfunction "PE13_66") (pintype "bidirectional"))
    )
    (net (code "103") (name "unconnected-(U1B-PE14-Pad67)") (class "Default")
      (node (ref "U1") (pin "67") (pinfunction "PE14_67") (pintype "bidirectional"))
    )
    (net (code "104") (name "unconnected-(U1B-PE15-Pad68)") (class "Default")
      (node (ref "U1") (pin "68") (pinfunction "PE15_68") (pintype "bidirectional"))
    )
    (net (code "105") (name "unconnected-(U1B-PF0-Pad10)") (class "Default")
      (node (ref "U1") (pin "10") (pinfunction "PF0_10") (pintype "bidirectional"))
    )
    (net (code "106") (name "unconnected-(U1B-PF1-Pad11)") (class "Default")
      (node (ref "U1") (pin "11") (pinfunction "PF1_11") (pintype "bidirectional"))
    )
    (net (code "107") (name "unconnected-(U1B-PF2-Pad12)") (class "Default")
      (node (ref "U1") (pin "12") (pinfunction "PF2_12") (pintype "bidirectional"))
    )
    (net (code "108") (name "unconnected-(U1B-PF3-Pad13)") (class "Default")
      (node (ref "U1") (pin "13") (pinfunction "PF3_13") (pintype "bidirectional"))
    )
    (net (code "109") (name "unconnected-(U1B-PF4-Pad14)") (class "Default")
      (node (ref "U1") (pin "14") (pinfunction "PF4_14") (pintype "bidirectional"))
    )
    (net (code "110") (name "unconnected-(U1B-PF5-Pad15)") (class "Default")
      (node (ref "U1") (pin "15") (pinfunction "PF5_15") (pintype "bidirectional"))
    )
    (net (code "111") (name "unconnected-(U1B-PF6-Pad18)") (class "Default")
      (node (ref "U1") (pin "18") (pinfunction "PF6_18") (pintype "bidirectional"))
    )
    (net (code "112") (name "unconnected-(U1B-PF7-Pad19)") (class "Default")
      (node (ref "U1") (pin "19") (pinfunction "PF7_19") (pintype "bidirectional"))
    )
    (net (code "113") (name "unconnected-(U1B-PF8-Pad20)") (class "Default")
      (node (ref "U1") (pin "20") (pinfunction "PF8_20") (pintype "bidirectional"))
    )
    (net (code "114") (name "unconnected-(U1B-PF9-Pad21)") (class "Default")
      (node (ref "U1") (pin "21") (pinfunction "PF9_21") (pintype "bidirectional"))
    )
    (net (code "115") (name "unconnected-(U1B-PF10-Pad22)") (class "Default")
      (node (ref "U1") (pin "22") (pinfunction "PF10_22") (pintype "bidirectional"))
    )
    (net (code "116") (name "unconnected-(U1B-PF11-Pad49)") (class "Default")
      (node (ref "U1") (pin "49") (pinfunction "PF11_49") (pintype "bidirectional"))
    )
    (net (code "117") (name "unconnected-(U1B-PF12-Pad50)") (class "Default")
      (node (ref "U1") (pin "50") (pinfunction "PF12_50") (pintype "bidirectional"))
    )
    (net (code "118") (name "unconnected-(U1B-PF13-Pad53)") (class "Default")
      (node (ref "U1") (pin "53") (pinfunction "PF13_53") (pintype "bidirectional"))
    )
    (net (code "119") (name "unconnected-(U1B-PF14-Pad54)") (class "Default")
      (node (ref "U1") (pin "54") (pinfunction "PF14_54") (pintype "bidirectional"))
    )
    (net (code "120") (name "unconnected-(U1B-PF15-Pad55)") (class "Default")
      (node (ref "U1") (pin "55") (pinfunction "PF15_55") (pintype "bidirectional"))
    )
    (net (code "121") (name "unconnected-(U1B-PG0-Pad56)") (class "Default")
      (node (ref "U1") (pin "56") (pinfunction "PG0_56") (pintype "bidirectional"))
    )
    (net (code "122") (name "unconnected-(U1B-PG1-Pad57)") (class "Default")
      (node (ref "U1") (pin "57") (pinfunction "PG1_57") (pintype "bidirectional"))
    )
    (net (code "123") (name "unconnected-(U1B-PG2-Pad87)") (class "Default")
      (node (ref "U1") (pin "87") (pinfunction "PG2_87") (pintype "bidirectional"))
    )
    (net (code "124") (name "unconnected-(U1B-PG3-Pad88)") (class "Default")
      (node (ref "U1") (pin "88") (pinfunction "PG3_88") (pintype "bidirectional"))
    )
    (net (code "125") (name "unconnected-(U1B-PG4-Pad89)") (class "Default")
      (node (ref "U1") (pin "89") (pinfunction "PG4_89") (pintype "bidirectional"))
    )
    (net (code "126") (name "unconnected-(U1B-PG5-Pad90)") (class "Default")
      (node (ref "U1") (pin "90") (pinfunction "PG5_90") (pintype "bidirectional"))
    )
    (net (code "127") (name "unconnected-(U1B-PG6-Pad91)") (class "Default")
      (node (ref "U1") (pin "91") (pinfunction "PG6_91") (pintype "bidirectional"))
    )
    (net (code "128") (name "unconnected-(U1B-PG7-Pad92)") (class "Default")
      (node (ref "U1") (pin "92") (pinfunction "PG7_92") (pintype "bidirectional"))
    )
    (net (code "129") (name "unconnected-(U1B-PG8-Pad93)") (class "Default")
      (node (ref "U1") (pin "93") (pinfunction "PG8_93") (pintype "bidirectional"))
    )
    (net (code "130") (name "unconnected-(U1B-PG9-Pad124)") (class "Default")
      (node (ref "U1") (pin "124") (pinfunction "PG9_124") (pintype "bidirectional"))
    )
    (net (code "131") (name "unconnected-(U1B-PG10-Pad125)") (class "Default")
      (node (ref "U1") (pin "125") (pinfunction "PG10_125") (pintype "bidirectional"))
    )
    (net (code "132") (name "unconnected-(U1B-PG11-Pad126)") (class "Default")
      (node (ref "U1") (pin "126") (pinfunction "PG11_126") (pintype "bidirectional"))
    )
    (net (code "133") (name "unconnected-(U1B-PG12-Pad127)") (class "Default")
      (node (ref "U1") (pin "127") (pinfunction "PG12_127") (pintype "bidirectional"))
    )
    (net (code "134") (name "unconnected-(U2-EH-Pad1)") (class "Default")
      (node (ref "U2") (pin "1") (pinfunction "EH_1") (pintype "passive+no_connect"))
    )
    (net (code "135") (name "unconnected-(U2-EH-Pad2)") (class "Default")
      (node (ref "U2") (pin "2") (pinfunction "EH_2") (pintype "passive+no_connect"))
    )
    (net (code "136") (name "unconnected-(U2-EH-Pad3)") (class "Default")
      (node (ref "U2") (pin "3") (pinfunction "EH_3") (pintype "passive+no_connect"))
    )
    (net (code "137") (name "unconnected-(U2-EH-Pad4)") (class "Default")
      (node (ref "U2") (pin "4") (pinfunction "EH_4") (pintype "passive+no_connect"))
    )
    (net (code "138") (name "unconnected-(U2-EH-Pad5)") (class "Default")
      (node (ref "U2") (pin "5") (pinfunction "EH_5") (pintype "passive+no_connect"))
    )
    (net (code "139") (name "unconnected-(U2-EH-Pad6)") (class "Default")
      (node (ref "U2") (pin "6") (pinfunction "EH_6") (pintype "passive+no_connect"))
    )
  )
)
